# TMC2130.net
KiCad netlist of a schematic drawn in Altium Designer
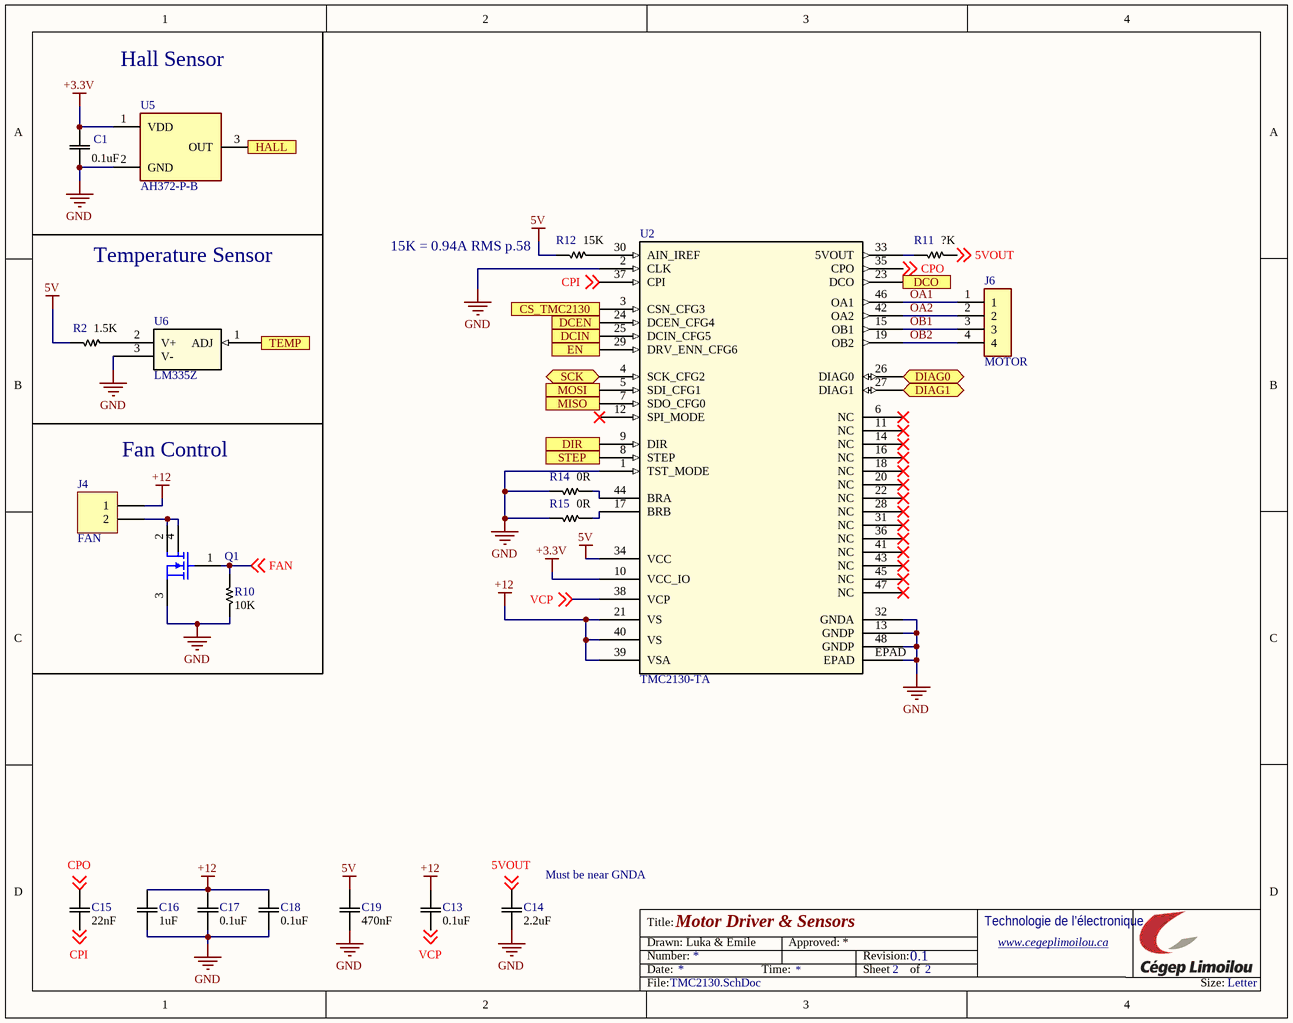
[diagram p0: TMC2130.SchDoc]

(export (version "E")
  (design (tool "Eeschema 10.0.6"))
  (components
    (comp (ref "C1")
      (value "0.1uF")
      (footprint "0603")
      (description "Capacitor SMD 0603")
      (fields
        (field (name "MANUFACTURER_PART_NUMBER") "12065A820JAT2A")
        (field (name "Comment") "Capacitor 0603")
        (field (name "COPYRIGHT") "Copyright (C) 2018 Accelerated Designs. All rights reserved")
      )
      (libsource (lib "Schematic_Emile") (part "Capacitor 1206"))
    )
    (comp (ref "C13")
      (value "0.1uF")
      (footprint "0603")
      (description "Capacitor SMD 0603")
      (fields
        (field (name "MANUFACTURER_PART_NUMBER") "12065A820JAT2A")
        (field (name "Comment") "Capacitor 0603")
        (field (name "COPYRIGHT") "Copyright (C) 2018 Accelerated Designs. All rights reserved")
      )
      (libsource (lib "Schematic_Emile") (part "Capacitor 1206"))
    )
    (comp (ref "C14")
      (value "2.2uF")
      (footprint "0603")
      (description "Capacitor SMD 0603")
      (fields
        (field (name "MANUFACTURER_PART_NUMBER") "12065A820JAT2A")
        (field (name "Comment") "Capacitor 0603")
        (field (name "COPYRIGHT") "Copyright (C) 2018 Accelerated Designs. All rights reserved")
      )
      (libsource (lib "Schematic_Emile") (part "Capacitor 1206"))
    )
    (comp (ref "C15")
      (value "22nF")
      (footprint "0603")
      (description "Capacitor SMD 0603")
      (fields
        (field (name "MANUFACTURER_PART_NUMBER") "12065A820JAT2A")
        (field (name "Comment") "Capacitor 0603")
        (field (name "COPYRIGHT") "Copyright (C) 2018 Accelerated Designs. All rights reserved")
      )
      (libsource (lib "Schematic_Emile") (part "Capacitor 1206"))
    )
    (comp (ref "C16")
      (value "1uF")
      (footprint "0603")
      (description "Capacitor SMD 0603")
      (fields
        (field (name "MANUFACTURER_PART_NUMBER") "12065A820JAT2A")
        (field (name "Comment") "Capacitor 0603")
        (field (name "COPYRIGHT") "Copyright (C) 2018 Accelerated Designs. All rights reserved")
      )
      (libsource (lib "Schematic_Emile") (part "Capacitor 1206"))
    )
    (comp (ref "C17")
      (value "0.1uF")
      (footprint "0603")
      (description "Capacitor SMD 0603")
      (fields
        (field (name "MANUFACTURER_PART_NUMBER") "12065A820JAT2A")
        (field (name "Comment") "Capacitor 0603")
        (field (name "COPYRIGHT") "Copyright (C) 2018 Accelerated Designs. All rights reserved")
      )
      (libsource (lib "Schematic_Emile") (part "Capacitor 1206"))
    )
    (comp (ref "C18")
      (value "0.1uF")
      (footprint "0603")
      (description "Capacitor SMD 0603")
      (fields
        (field (name "MANUFACTURER_PART_NUMBER") "12065A820JAT2A")
        (field (name "Comment") "Capacitor 0603")
        (field (name "COPYRIGHT") "Copyright (C) 2018 Accelerated Designs. All rights reserved")
      )
      (libsource (lib "Schematic_Emile") (part "Capacitor 1206"))
    )
    (comp (ref "C19")
      (value "470nF")
      (footprint "0603")
      (description "Capacitor SMD 0603")
      (fields
        (field (name "MANUFACTURER_PART_NUMBER") "12065A820JAT2A")
        (field (name "Comment") "Capacitor 0603")
        (field (name "COPYRIGHT") "Copyright (C) 2018 Accelerated Designs. All rights reserved")
      )
      (libsource (lib "Schematic_Emile") (part "Capacitor 1206"))
    )
    (comp (ref "J4")
      (value "FAN")
      (footprint "HDR1X2")
      (description "Header, 2-Pin")
      (fields (field (name "PUBLISHER") "Altium Limited"))
      (libsource (lib "Miscellaneous Connectors") (part "Header 2"))
    )
    (comp (ref "J6")
      (value "MOTOR")
      (footprint "JST 4POS 2.5mm 90°")
      (description "Connector")
      (fields
        (field (name "MANUFACTURER_PART_NUMBER") "S4B-XH-A(LF)(SN)")
        (field (name "RS PART NUMBER") "8201589P")
      )
      (libsource (lib "Schematic_Emile") (part "JST 4POS"))
    )
    (comp (ref "Q1")
      (value "MOSFET N-CH")
      (footprint "SOT223_M")
      (description "55V 7A SOT223")
      (libsource (lib "Schematic_Emile") (part "MOSFET N-CH"))
    )
    (comp (ref "R2")
      (value "1.5K")
      (footprint "0603")
      (description "Resistor 0603 SMD")
      (fields
        (field (name "MANUFACTURER_PART_NUMBER") "ERJ8CWFR024V")
        (field (name "Comment") "Resistor 0603")
        (field (name "COPYRIGHT") "Copyright (C) 2018 Accelerated Designs. All rights reserved")
      )
      (libsource (lib "Schematic_Emile") (part "Resistor 1206"))
    )
    (comp (ref "R10")
      (value "10K")
      (footprint "0603")
      (description "Resistor 0603 SMD")
      (fields
        (field (name "MANUFACTURER_PART_NUMBER") "ERJ8CWFR024V")
        (field (name "Comment") "Resistor 0603")
        (field (name "COPYRIGHT") "Copyright (C) 2018 Accelerated Designs. All rights reserved")
      )
      (libsource (lib "Schematic_Emile") (part "Resistor 1206"))
    )
    (comp (ref "R11")
      (value "?K")
      (footprint "0603")
      (description "Resistor 0603 SMD")
      (fields
        (field (name "MANUFACTURER_PART_NUMBER") "ERJ8CWFR024V")
        (field (name "Comment") "Resistor 0603")
        (field (name "COPYRIGHT") "Copyright (C) 2018 Accelerated Designs. All rights reserved")
      )
      (libsource (lib "Schematic_Emile") (part "Resistor 1206"))
    )
    (comp (ref "R12")
      (value "15K")
      (footprint "0603")
      (description "Resistor 0603 SMD")
      (fields
        (field (name "MANUFACTURER_PART_NUMBER") "ERJ8CWFR024V")
        (field (name "Comment") "Resistor 0603")
        (field (name "COPYRIGHT") "Copyright (C) 2018 Accelerated Designs. All rights reserved")
      )
      (libsource (lib "Schematic_Emile") (part "Resistor 1206"))
    )
    (comp (ref "R14")
      (value "0R")
      (footprint "0603")
      (description "Resistor 0603 SMD")
      (fields
        (field (name "MANUFACTURER_PART_NUMBER") "ERJ8CWFR024V")
        (field (name "Comment") "Resistor 0603")
        (field (name "COPYRIGHT") "Copyright (C) 2018 Accelerated Designs. All rights reserved")
      )
      (libsource (lib "Schematic_Emile") (part "Resistor 1206"))
    )
    (comp (ref "R15")
      (value "0R")
      (footprint "0603")
      (description "Resistor 0603 SMD")
      (fields
        (field (name "MANUFACTURER_PART_NUMBER") "ERJ8CWFR024V")
        (field (name "Comment") "Resistor 0603")
        (field (name "COPYRIGHT") "Copyright (C) 2018 Accelerated Designs. All rights reserved")
      )
      (libsource (lib "Schematic_Emile") (part "Resistor 1206"))
    )
    (comp (ref "U2")
      (value "TMC2130-TA")
      (footprint "eTQFP48_9x9")
      (description "Motor Driver TMC2130")
      (fields (field (name "COPYRIGHT") "Copyright (C) 2016 Accelerated Designs. All rights reserved"))
      (libsource (lib "Schematic_Emile") (part "TMC2130-TA"))
    )
    (comp (ref "U5")
      (value "AH372-P-B")
      (footprint "Footprint_Emile:AH372PB")
      (description "Hall Sensor")
      (fields (field (name "MOUSER PART NUMBER") "621-AH372-P-B") (field (name "RS PART NUMBER") "1333361P"))
      (libsource (lib "Schematic_Emile") (part "AH372-P-B"))
    )
    (comp (ref "U6")
      (value "LM335Z")
      (footprint "TO92")
      (description "Temperature Sensor")
      (fields (field (name "COPYRIGHT") "Copyright (C) 2018 Accelerated Designs. All rights reserved"))
      (libsource (lib "Schematic_Emile") (part "LM335Z"))
    )
  )
  (nets
    (net (code "1") (name "+3.3V") (class "Default")
      (node (ref "C1") (pin "2") (pinfunction "2_2") (pintype "passive"))
      (node (ref "U2") (pin "10") (pinfunction "VCC_IO_10") (pintype "power_in"))
      (node (ref "U5") (pin "1") (pinfunction "VDD_1") (pintype "passive"))
    )
    (net (code "2") (name "+12") (class "Default")
      (node (ref "C13") (pin "2") (pinfunction "2_2") (pintype "passive"))
      (node (ref "C16") (pin "2") (pinfunction "2_2") (pintype "passive"))
      (node (ref "C17") (pin "2") (pinfunction "2_2") (pintype "passive"))
      (node (ref "C18") (pin "2") (pinfunction "2_2") (pintype "passive"))
      (node (ref "J4") (pin "1") (pinfunction "1_1") (pintype "passive"))
      (node (ref "U2") (pin "21") (pinfunction "VS_21") (pintype "power_in"))
      (node (ref "U2") (pin "39") (pinfunction "VSA_39") (pintype "power_in"))
      (node (ref "U2") (pin "40") (pinfunction "VS_40") (pintype "power_in"))
    )
    (net (code "3") (name "/CS_TMC2130") (class "Default")
      (node (ref "U2") (pin "3") (pinfunction "CSN_CFG3_3") (pintype "input"))
    )
    (net (code "4") (name "/DCEN") (class "Default")
      (node (ref "U2") (pin "24") (pinfunction "DCEN_CFG4_24") (pintype "input"))
    )
    (net (code "5") (name "/DCIN") (class "Default")
      (node (ref "U2") (pin "25") (pinfunction "DCIN_CFG5_25") (pintype "input"))
    )
    (net (code "6") (name "/DCO") (class "Default")
      (node (ref "U2") (pin "23") (pinfunction "DCO_23") (pintype "output"))
    )
    (net (code "7") (name "/DIAG0") (class "Default")
      (node (ref "U2") (pin "26") (pinfunction "DIAG0_26") (pintype "bidirectional"))
    )
    (net (code "8") (name "/DIAG1") (class "Default")
      (node (ref "U2") (pin "27") (pinfunction "DIAG1_27") (pintype "bidirectional"))
    )
    (net (code "9") (name "/DIR") (class "Default")
      (node (ref "U2") (pin "9") (pinfunction "DIR_9") (pintype "input"))
    )
    (net (code "10") (name "/EN") (class "Default")
      (node (ref "U2") (pin "29") (pinfunction "DRV_ENN_CFG6_29") (pintype "input"))
    )
    (net (code "11") (name "/HALL") (class "Default")
      (node (ref "U5") (pin "3") (pinfunction "OUT_3") (pintype "passive"))
    )
    (net (code "12") (name "/MISO") (class "Default")
      (node (ref "U2") (pin "7") (pinfunction "SDO_CFG0_7") (pintype "input"))
    )
    (net (code "13") (name "/MOSI") (class "Default")
      (node (ref "U2") (pin "5") (pinfunction "SDI_CFG1_5") (pintype "input"))
    )
    (net (code "14") (name "/OA1") (class "Default")
      (node (ref "J6") (pin "1") (pinfunction "1_1") (pintype "passive"))
      (node (ref "U2") (pin "46") (pinfunction "OA1_46") (pintype "output"))
    )
    (net (code "15") (name "/OA2") (class "Default")
      (node (ref "J6") (pin "2") (pinfunction "2_2") (pintype "passive"))
      (node (ref "U2") (pin "42") (pinfunction "OA2_42") (pintype "output"))
    )
    (net (code "16") (name "/OB1") (class "Default")
      (node (ref "J6") (pin "3") (pinfunction "3_3") (pintype "passive"))
      (node (ref "U2") (pin "15") (pinfunction "OB1_15") (pintype "output"))
    )
    (net (code "17") (name "/OB2") (class "Default")
      (node (ref "J6") (pin "4") (pinfunction "4_4") (pintype "passive"))
      (node (ref "U2") (pin "19") (pinfunction "OB2_19") (pintype "output"))
    )
    (net (code "18") (name "/SCK") (class "Default")
      (node (ref "U2") (pin "4") (pinfunction "SCK_CFG2_4") (pintype "input"))
    )
    (net (code "19") (name "/STEP") (class "Default")
      (node (ref "U2") (pin "8") (pinfunction "STEP_8") (pintype "input"))
    )
    (net (code "20") (name "/TEMP") (class "Default")
      (node (ref "U6") (pin "1") (pinfunction "ADJ_1") (pintype "input"))
    )
    (net (code "21") (name "5V") (class "Default")
      (node (ref "C19") (pin "2") (pinfunction "2_2") (pintype "passive"))
      (node (ref "R12") (pin "1") (pinfunction "1_1") (pintype "passive"))
      (node (ref "R2") (pin "1") (pinfunction "1_1") (pintype "passive"))
      (node (ref "U2") (pin "34") (pinfunction "VCC_34") (pintype "power_in"))
    )
    (net (code "22") (name "5VOUT") (class "Default")
      (node (ref "C14") (pin "2") (pinfunction "2_2") (pintype "passive"))
      (node (ref "R11") (pin "2") (pinfunction "2_2") (pintype "passive"))
    )
    (net (code "23") (name "CPI") (class "Default")
      (node (ref "C15") (pin "1") (pinfunction "1_1") (pintype "passive"))
      (node (ref "U2") (pin "37") (pinfunction "CPI_37") (pintype "input"))
    )
    (net (code "24") (name "CPO") (class "Default")
      (node (ref "C15") (pin "2") (pinfunction "2_2") (pintype "passive"))
      (node (ref "U2") (pin "35") (pinfunction "CPO_35") (pintype "output"))
    )
    (net (code "25") (name "FAN") (class "Default")
      (node (ref "Q1") (pin "1") (pinfunction "G_1") (pintype "passive"))
      (node (ref "R10") (pin "2") (pinfunction "2_2") (pintype "passive"))
    )
    (net (code "26") (name "GND") (class "Default")
      (node (ref "C1") (pin "1") (pinfunction "1_1") (pintype "passive"))
      (node (ref "C14") (pin "1") (pinfunction "1_1") (pintype "passive"))
      (node (ref "C16") (pin "1") (pinfunction "1_1") (pintype "passive"))
      (node (ref "C17") (pin "1") (pinfunction "1_1") (pintype "passive"))
      (node (ref "C18") (pin "1") (pinfunction "1_1") (pintype "passive"))
      (node (ref "C19") (pin "1") (pinfunction "1_1") (pintype "passive"))
      (node (ref "Q1") (pin "3") (pinfunction "S_3") (pintype "passive"))
      (node (ref "R10") (pin "1") (pinfunction "1_1") (pintype "passive"))
      (node (ref "R14") (pin "1") (pinfunction "1_1") (pintype "passive"))
      (node (ref "R15") (pin "1") (pinfunction "1_1") (pintype "passive"))
      (node (ref "U2") (pin "1") (pinfunction "TST_MODE_1") (pintype "input"))
      (node (ref "U2") (pin "13") (pinfunction "GNDP_13") (pintype "power_in"))
      (node (ref "U2") (pin "2") (pinfunction "CLK_2") (pintype "input"))
      (node (ref "U2") (pin "32") (pinfunction "GNDA_32") (pintype "power_in"))
      (node (ref "U2") (pin "48") (pinfunction "GNDP_48") (pintype "power_in"))
      (node (ref "U2") (pin "EPAD") (pinfunction "EPAD_EPAD") (pintype "passive"))
      (node (ref "U5") (pin "2") (pinfunction "GND_2") (pintype "passive"))
      (node (ref "U6") (pin "3") (pinfunction "V-_3") (pintype "power_in"))
    )
    (net (code "27") (name "Net-(J4-Pad2)") (class "Default")
      (node (ref "J4") (pin "2") (pinfunction "2_2") (pintype "passive"))
      (node (ref "Q1") (pin "2") (pinfunction "D_2") (pintype "passive"))
      (node (ref "Q1") (pin "4") (pinfunction "D_4") (pintype "passive"))
    )
    (net (code "28") (name "Net-(U2-5VOUT)") (class "Default")
      (node (ref "R11") (pin "1") (pinfunction "1_1") (pintype "passive"))
      (node (ref "U2") (pin "33") (pinfunction "5VOUT_33") (pintype "output"))
    )
    (net (code "29") (name "Net-(U2-AIN_IREF)") (class "Default")
      (node (ref "R12") (pin "2") (pinfunction "2_2") (pintype "passive"))
      (node (ref "U2") (pin "30") (pinfunction "AIN_IREF_30") (pintype "input"))
    )
    (net (code "30") (name "Net-(U2-BRA)") (class "Default")
      (node (ref "R14") (pin "2") (pinfunction "2_2") (pintype "passive"))
      (node (ref "U2") (pin "44") (pinfunction "BRA_44") (pintype "passive"))
    )
    (net (code "31") (name "Net-(U2-BRB)") (class "Default")
      (node (ref "R15") (pin "2") (pinfunction "2_2") (pintype "passive"))
      (node (ref "U2") (pin "17") (pinfunction "BRB_17") (pintype "passive"))
    )
    (net (code "32") (name "Net-(U6-V+)") (class "Default")
      (node (ref "R2") (pin "2") (pinfunction "2_2") (pintype "passive"))
      (node (ref "U6") (pin "2") (pinfunction "V+_2") (pintype "power_in"))
    )
    (net (code "33") (name "VCP") (class "Default")
      (node (ref "C13") (pin "1") (pinfunction "1_1") (pintype "passive"))
      (node (ref "U2") (pin "38") (pinfunction "VCP_38") (pintype "power_in"))
    )
    (net (code "34") (name "unconnected-(U2-NC-Pad6)") (class "Default")
      (node (ref "U2") (pin "6") (pinfunction "NC_6") (pintype "passive+no_connect"))
    )
    (net (code "35") (name "unconnected-(U2-NC-Pad11)") (class "Default")
      (node (ref "U2") (pin "11") (pinfunction "NC_11") (pintype "passive+no_connect"))
    )
    (net (code "36") (name "unconnected-(U2-NC-Pad14)") (class "Default")
      (node (ref "U2") (pin "14") (pinfunction "NC_14") (pintype "passive+no_connect"))
    )
    (net (code "37") (name "unconnected-(U2-NC-Pad16)") (class "Default")
      (node (ref "U2") (pin "16") (pinfunction "NC_16") (pintype "passive+no_connect"))
    )
    (net (code "38") (name "unconnected-(U2-NC-Pad18)") (class "Default")
      (node (ref "U2") (pin "18") (pinfunction "NC_18") (pintype "passive+no_connect"))
    )
    (net (code "39") (name "unconnected-(U2-NC-Pad20)") (class "Default")
      (node (ref "U2") (pin "20") (pinfunction "NC_20") (pintype "passive+no_connect"))
    )
    (net (code "40") (name "unconnected-(U2-NC-Pad22)") (class "Default")
      (node (ref "U2") (pin "22") (pinfunction "NC_22") (pintype "passive+no_connect"))
    )
    (net (code "41") (name "unconnected-(U2-NC-Pad28)") (class "Default")
      (node (ref "U2") (pin "28") (pinfunction "NC_28") (pintype "passive+no_connect"))
    )
    (net (code "42") (name "unconnected-(U2-NC-Pad31)") (class "Default")
      (node (ref "U2") (pin "31") (pinfunction "NC_31") (pintype "passive+no_connect"))
    )
    (net (code "43") (name "unconnected-(U2-NC-Pad36)") (class "Default")
      (node (ref "U2") (pin "36") (pinfunction "NC_36") (pintype "passive+no_connect"))
    )
    (net (code "44") (name "unconnected-(U2-NC-Pad41)") (class "Default")
      (node (ref "U2") (pin "41") (pinfunction "NC_41") (pintype "passive+no_connect"))
    )
    (net (code "45") (name "unconnected-(U2-NC-Pad43)") (class "Default")
      (node (ref "U2") (pin "43") (pinfunction "NC_43") (pintype "passive+no_connect"))
    )
    (net (code "46") (name "unconnected-(U2-NC-Pad45)") (class "Default")
      (node (ref "U2") (pin "45") (pinfunction "NC_45") (pintype "passive+no_connect"))
    )
    (net (code "47") (name "unconnected-(U2-NC-Pad47)") (class "Default")
      (node (ref "U2") (pin "47") (pinfunction "NC_47") (pintype "passive+no_connect"))
    )
    (net (code "48") (name "unconnected-(U2-SPI_MODE-Pad12)") (class "Default")
      (node (ref "U2") (pin "12") (pinfunction "SPI_MODE_12") (pintype "input+no_connect"))
    )
  )
)
